# ProcessingModule.net
KiCad netlist of a schematic drawn in EAGLE
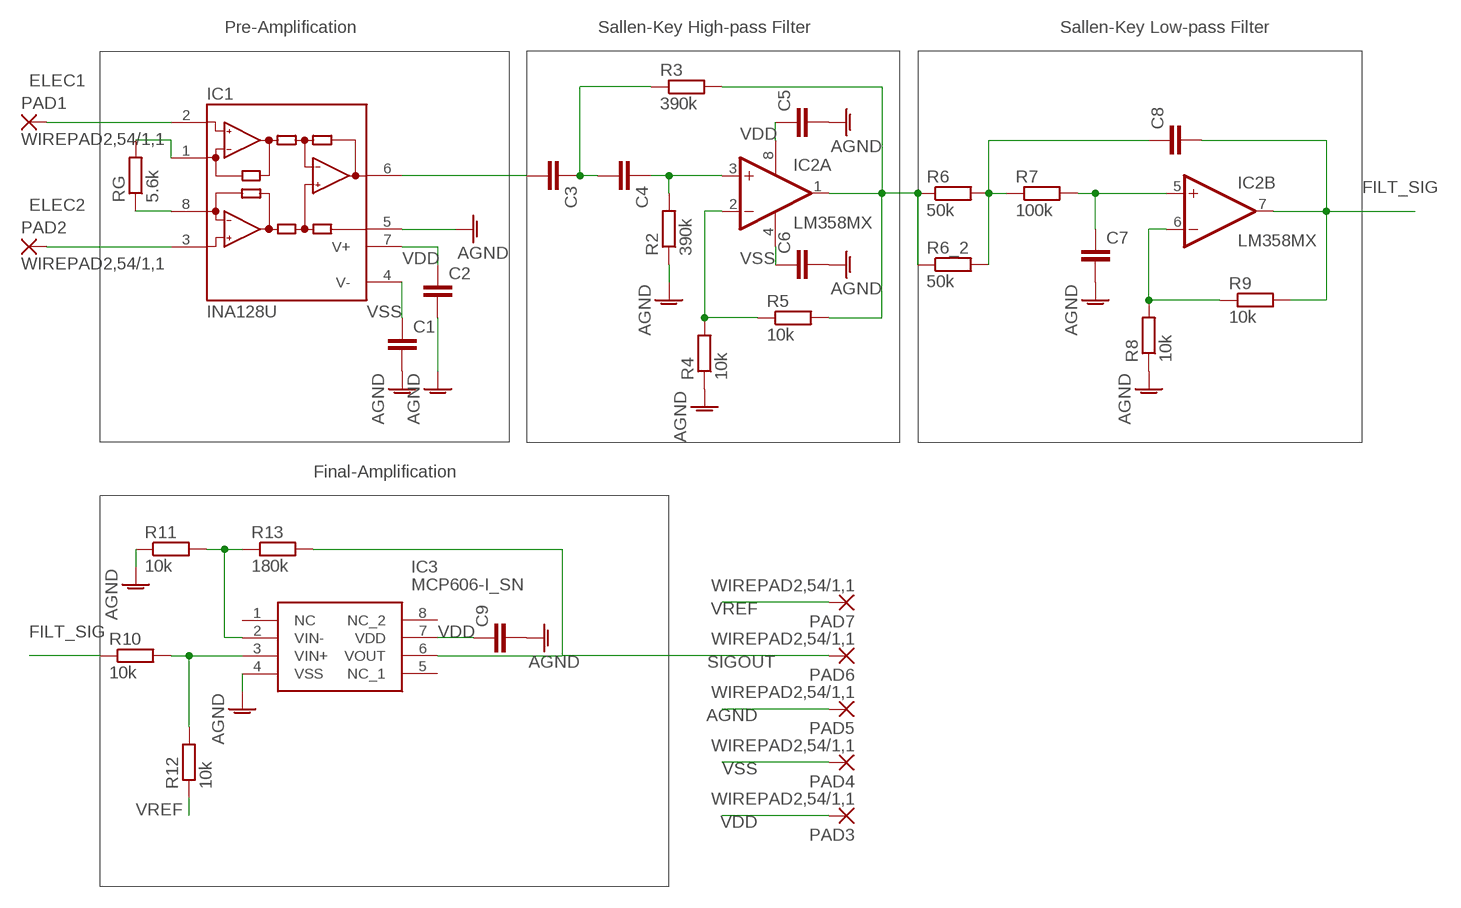
[diagram p0: schematic, sheet 1]

(export (version "E")
  (design (tool "Eeschema 10.0.6"))
  (components
    (comp (ref "C1")
      (value "C-EUC0603")
      (footprint "eagle-import:C0603")
      (libsource (lib "eagle-import") (part "C-EUC0603"))
    )
    (comp (ref "C2")
      (value "C-EUC0603")
      (footprint "eagle-import:C0603")
      (libsource (lib "eagle-import") (part "C-EUC0603"))
    )
    (comp (ref "C3")
      (value "C-EUC0603")
      (footprint "eagle-import:C0603")
      (libsource (lib "eagle-import") (part "C-EUC0603"))
    )
    (comp (ref "C4")
      (value "C-EUC0603")
      (footprint "eagle-import:C0603")
      (libsource (lib "eagle-import") (part "C-EUC0603"))
    )
    (comp (ref "C5")
      (value "C-EUC0603")
      (footprint "eagle-import:C0603")
      (libsource (lib "eagle-import") (part "C-EUC0603"))
    )
    (comp (ref "C6")
      (value "C-EUC0603")
      (footprint "eagle-import:C0603")
      (libsource (lib "eagle-import") (part "C-EUC0603"))
    )
    (comp (ref "C7")
      (value "C-EUC0603")
      (footprint "eagle-import:C0603")
      (libsource (lib "eagle-import") (part "C-EUC0603"))
    )
    (comp (ref "C8")
      (value "C-EUC0603")
      (footprint "eagle-import:C0603")
      (libsource (lib "eagle-import") (part "C-EUC0603"))
    )
    (comp (ref "C9")
      (value "C-EUC0603")
      (footprint "eagle-import:C0603")
      (libsource (lib "eagle-import") (part "C-EUC0603"))
    )
    (comp (ref "IC1")
      (value "INA128U")
      (footprint "eagle-import:SO08")
      (fields (field (name "MF") "TEXAS INSTRUMENTS"))
      (libsource (lib "eagle-import") (part "INA128U"))
    )
    (comp (ref "IC2")
      (value "LM358MX")
      (footprint "eagle-import:SO08")
      (fields (field (name "SPICEPREFIX") "J"))
      (libsource (lib "eagle-import") (part "LM358MX"))
    )
    (comp (ref "IC3")
      (value "MCP606-I_SN")
      (footprint "eagle-import:SOIC127P600X175-8N")
      (fields (field (name "ARROW_PART_NUMBER") "MCP606-I/SN") (field (name "RS_PART_NUMBER") "0403002P"))
      (libsource (lib "eagle-import") (part "MCP606-I_SN"))
    )
    (comp (ref "PAD1")
      (value "WIREPAD2,54/1,1")
      (footprint "eagle-import:2,54_1,1")
      (libsource (lib "eagle-import") (part "WIREPAD2,54/1,1"))
    )
    (comp (ref "PAD2")
      (value "WIREPAD2,54/1,1")
      (footprint "eagle-import:2,54_1,1")
      (libsource (lib "eagle-import") (part "WIREPAD2,54/1,1"))
    )
    (comp (ref "PAD3")
      (value "WIREPAD2,54/1,1")
      (footprint "eagle-import:2,54_1,1")
      (libsource (lib "eagle-import") (part "WIREPAD2,54/1,1"))
    )
    (comp (ref "PAD4")
      (value "WIREPAD2,54/1,1")
      (footprint "eagle-import:2,54_1,1")
      (libsource (lib "eagle-import") (part "WIREPAD2,54/1,1"))
    )
    (comp (ref "PAD5")
      (value "WIREPAD2,54/1,1")
      (footprint "eagle-import:2,54_1,1")
      (libsource (lib "eagle-import") (part "WIREPAD2,54/1,1"))
    )
    (comp (ref "PAD6")
      (value "WIREPAD2,54/1,1")
      (footprint "eagle-import:2,54_1,1")
      (libsource (lib "eagle-import") (part "WIREPAD2,54/1,1"))
    )
    (comp (ref "PAD7")
      (value "WIREPAD2,54/1,1")
      (footprint "eagle-import:2,54_1,1")
      (libsource (lib "eagle-import") (part "WIREPAD2,54/1,1"))
    )
    (comp (ref "R2")
      (value "390k")
      (footprint "eagle-import:R0805")
      (libsource (lib "eagle-import") (part "R-EU_R0805"))
    )
    (comp (ref "R3")
      (value "390k")
      (footprint "eagle-import:R0805")
      (libsource (lib "eagle-import") (part "R-EU_R0805"))
    )
    (comp (ref "R4")
      (value "10k")
      (footprint "eagle-import:R0805")
      (libsource (lib "eagle-import") (part "R-EU_R0805"))
    )
    (comp (ref "R5")
      (value "10k")
      (footprint "eagle-import:R0805")
      (libsource (lib "eagle-import") (part "R-EU_R0805"))
    )
    (comp (ref "R6")
      (value "50k")
      (footprint "eagle-import:R0805")
      (libsource (lib "eagle-import") (part "R-EU_R0805"))
    )
    (comp (ref "R6_2")
      (value "50k")
      (footprint "eagle-import:R0805")
      (libsource (lib "eagle-import") (part "R-EU_R0805"))
    )
    (comp (ref "R7")
      (value "100k")
      (footprint "eagle-import:R0805")
      (libsource (lib "eagle-import") (part "R-EU_R0805"))
    )
    (comp (ref "R8")
      (value "10k")
      (footprint "eagle-import:R0805")
      (libsource (lib "eagle-import") (part "R-EU_R0805"))
    )
    (comp (ref "R9")
      (value "10k")
      (footprint "eagle-import:R0805")
      (libsource (lib "eagle-import") (part "R-EU_R0805"))
    )
    (comp (ref "R10")
      (value "10k")
      (footprint "eagle-import:R0805")
      (libsource (lib "eagle-import") (part "R-EU_R0805"))
    )
    (comp (ref "R11")
      (value "10k")
      (footprint "eagle-import:R0805")
      (libsource (lib "eagle-import") (part "R-EU_R0805"))
    )
    (comp (ref "R12")
      (value "10k")
      (footprint "eagle-import:R0805")
      (libsource (lib "eagle-import") (part "R-EU_R0805"))
    )
    (comp (ref "R13")
      (value "180k")
      (footprint "eagle-import:R0805")
      (libsource (lib "eagle-import") (part "R-EU_R0805"))
    )
    (comp (ref "RG")
      (value "5.6k")
      (footprint "eagle-import:R0805")
      (libsource (lib "eagle-import") (part "R-EU_R0805"))
    )
  )
  (nets
    (net (code "1") (name "/ELEC1") (class "Default")
      (node (ref "IC1") (pin "2") (pinfunction "-IN_2") (pintype "input"))
      (node (ref "PAD1") (pin "1") (pinfunction "P_1") (pintype "passive"))
    )
    (net (code "2") (name "/ELEC2") (class "Default")
      (node (ref "IC1") (pin "3") (pinfunction "+IN_3") (pintype "input"))
      (node (ref "PAD2") (pin "1") (pinfunction "P_1") (pintype "passive"))
    )
    (net (code "3") (name "/FILT_SIG") (class "Default")
      (node (ref "C8") (pin "2") (pinfunction "2_2") (pintype "passive"))
      (node (ref "IC2") (pin "7") (pinfunction "OUT_7") (pintype "output"))
      (node (ref "R10") (pin "1") (pinfunction "1_1") (pintype "passive"))
      (node (ref "R9") (pin "2") (pinfunction "2_2") (pintype "passive"))
    )
    (net (code "4") (name "/SIGOUT") (class "Default")
      (node (ref "IC3") (pin "6") (pinfunction "VOUT_6") (pintype "output"))
      (node (ref "PAD6") (pin "1") (pinfunction "P_1") (pintype "passive"))
      (node (ref "R13") (pin "2") (pinfunction "2_2") (pintype "passive"))
    )
    (net (code "5") (name "/VDD") (class "Default")
      (node (ref "C2") (pin "1") (pinfunction "1_1") (pintype "passive"))
      (node (ref "C5") (pin "1") (pinfunction "1_1") (pintype "passive"))
      (node (ref "C9") (pin "1") (pinfunction "1_1") (pintype "passive"))
      (node (ref "IC1") (pin "7") (pinfunction "V+_7") (pintype "power_in"))
      (node (ref "IC2") (pin "8") (pinfunction "V+_8") (pintype "power_in"))
      (node (ref "IC3") (pin "7") (pinfunction "VDD_7") (pintype "power_in"))
      (node (ref "PAD3") (pin "1") (pinfunction "P_1") (pintype "passive"))
    )
    (net (code "6") (name "/VREF") (class "Default")
      (node (ref "PAD7") (pin "1") (pinfunction "P_1") (pintype "passive"))
      (node (ref "R12") (pin "1") (pinfunction "1_1") (pintype "passive"))
    )
    (net (code "7") (name "/VSS") (class "Default")
      (node (ref "C1") (pin "1") (pinfunction "1_1") (pintype "passive"))
      (node (ref "C6") (pin "1") (pinfunction "1_1") (pintype "passive"))
      (node (ref "IC1") (pin "4") (pinfunction "V-_4") (pintype "power_in"))
      (node (ref "IC2") (pin "4") (pinfunction "V-_4") (pintype "power_in"))
      (node (ref "PAD4") (pin "1") (pinfunction "P_1") (pintype "passive"))
    )
    (net (code "8") (name "AGND") (class "Default")
      (node (ref "C1") (pin "2") (pinfunction "2_2") (pintype "passive"))
      (node (ref "C2") (pin "2") (pinfunction "2_2") (pintype "passive"))
      (node (ref "C5") (pin "2") (pinfunction "2_2") (pintype "passive"))
      (node (ref "C6") (pin "2") (pinfunction "2_2") (pintype "passive"))
      (node (ref "C7") (pin "2") (pinfunction "2_2") (pintype "passive"))
      (node (ref "C9") (pin "2") (pinfunction "2_2") (pintype "passive"))
      (node (ref "IC1") (pin "5") (pinfunction "REF_5") (pintype "passive"))
      (node (ref "IC3") (pin "4") (pinfunction "VSS_4") (pintype "power_in"))
      (node (ref "PAD5") (pin "1") (pinfunction "P_1") (pintype "passive"))
      (node (ref "R11") (pin "1") (pinfunction "1_1") (pintype "passive"))
      (node (ref "R2") (pin "1") (pinfunction "1_1") (pintype "passive"))
      (node (ref "R4") (pin "1") (pinfunction "1_1") (pintype "passive"))
      (node (ref "R8") (pin "1") (pinfunction "1_1") (pintype "passive"))
    )
    (net (code "9") (name "Net-(C3-Pad1)") (class "Default")
      (node (ref "C3") (pin "1") (pinfunction "1_1") (pintype "passive"))
      (node (ref "C4") (pin "2") (pinfunction "2_2") (pintype "passive"))
      (node (ref "R3") (pin "1") (pinfunction "1_1") (pintype "passive"))
    )
    (net (code "10") (name "Net-(C8-Pad1)") (class "Default")
      (node (ref "C8") (pin "1") (pinfunction "1_1") (pintype "passive"))
      (node (ref "R6") (pin "2") (pinfunction "2_2") (pintype "passive"))
      (node (ref "R6_2") (pin "2") (pinfunction "2_2") (pintype "passive"))
      (node (ref "R7") (pin "1") (pinfunction "1_1") (pintype "passive"))
    )
    (net (code "11") (name "Net-(IC1-OUT)") (class "Default")
      (node (ref "C3") (pin "2") (pinfunction "2_2") (pintype "passive"))
      (node (ref "IC1") (pin "6") (pinfunction "OUT_6") (pintype "output"))
    )
    (net (code "12") (name "Net-(IC1-RG-Pad1)") (class "Default")
      (node (ref "IC1") (pin "1") (pinfunction "RG_1") (pintype "passive"))
      (node (ref "RG") (pin "2") (pinfunction "2_2") (pintype "passive"))
    )
    (net (code "13") (name "Net-(IC1-RG-Pad8)") (class "Default")
      (node (ref "IC1") (pin "8") (pinfunction "RG_8") (pintype "passive"))
      (node (ref "RG") (pin "1") (pinfunction "1_1") (pintype "passive"))
    )
    (net (code "14") (name "Net-(IC2A-+IN)") (class "Default")
      (node (ref "C4") (pin "1") (pinfunction "1_1") (pintype "passive"))
      (node (ref "IC2") (pin "3") (pinfunction "+IN_3") (pintype "input"))
      (node (ref "R2") (pin "2") (pinfunction "2_2") (pintype "passive"))
    )
    (net (code "15") (name "Net-(IC2A--IN)") (class "Default")
      (node (ref "IC2") (pin "2") (pinfunction "-IN_2") (pintype "input"))
      (node (ref "R4") (pin "2") (pinfunction "2_2") (pintype "passive"))
      (node (ref "R5") (pin "1") (pinfunction "1_1") (pintype "passive"))
    )
    (net (code "16") (name "Net-(IC2A-OUT)") (class "Default")
      (node (ref "IC2") (pin "1") (pinfunction "OUT_1") (pintype "output"))
      (node (ref "R3") (pin "2") (pinfunction "2_2") (pintype "passive"))
      (node (ref "R5") (pin "2") (pinfunction "2_2") (pintype "passive"))
      (node (ref "R6") (pin "1") (pinfunction "1_1") (pintype "passive"))
      (node (ref "R6_2") (pin "1") (pinfunction "1_1") (pintype "passive"))
    )
    (net (code "17") (name "Net-(IC2B-+IN)") (class "Default")
      (node (ref "C7") (pin "1") (pinfunction "1_1") (pintype "passive"))
      (node (ref "IC2") (pin "5") (pinfunction "+IN_5") (pintype "input"))
      (node (ref "R7") (pin "2") (pinfunction "2_2") (pintype "passive"))
    )
    (net (code "18") (name "Net-(IC2B--IN)") (class "Default")
      (node (ref "IC2") (pin "6") (pinfunction "-IN_6") (pintype "input"))
      (node (ref "R8") (pin "2") (pinfunction "2_2") (pintype "passive"))
      (node (ref "R9") (pin "1") (pinfunction "1_1") (pintype "passive"))
    )
    (net (code "19") (name "Net-(IC3-VIN+)") (class "Default")
      (node (ref "IC3") (pin "3") (pinfunction "VIN+_3") (pintype "input"))
      (node (ref "R10") (pin "2") (pinfunction "2_2") (pintype "passive"))
      (node (ref "R12") (pin "2") (pinfunction "2_2") (pintype "passive"))
    )
    (net (code "20") (name "Net-(IC3-VIN-)") (class "Default")
      (node (ref "IC3") (pin "2") (pinfunction "VIN-_2") (pintype "input"))
      (node (ref "R11") (pin "2") (pinfunction "2_2") (pintype "passive"))
      (node (ref "R13") (pin "1") (pinfunction "1_1") (pintype "passive"))
    )
    (net (code "21") (name "unconnected-(IC3-NC-Pad1)") (class "Default")
      (node (ref "IC3") (pin "1") (pinfunction "NC_1") (pintype "no_connect"))
    )
    (net (code "22") (name "unconnected-(IC3-NC_1-Pad5)") (class "Default")
      (node (ref "IC3") (pin "5") (pinfunction "NC_1_5") (pintype "bidirectional"))
    )
    (net (code "23") (name "unconnected-(IC3-NC_2-Pad8)") (class "Default")
      (node (ref "IC3") (pin "8") (pinfunction "NC_2_8") (pintype "bidirectional"))
    )
  )
)
